# 20_FPGA_Power.net
KiCad netlist of a schematic drawn in Altium Designer
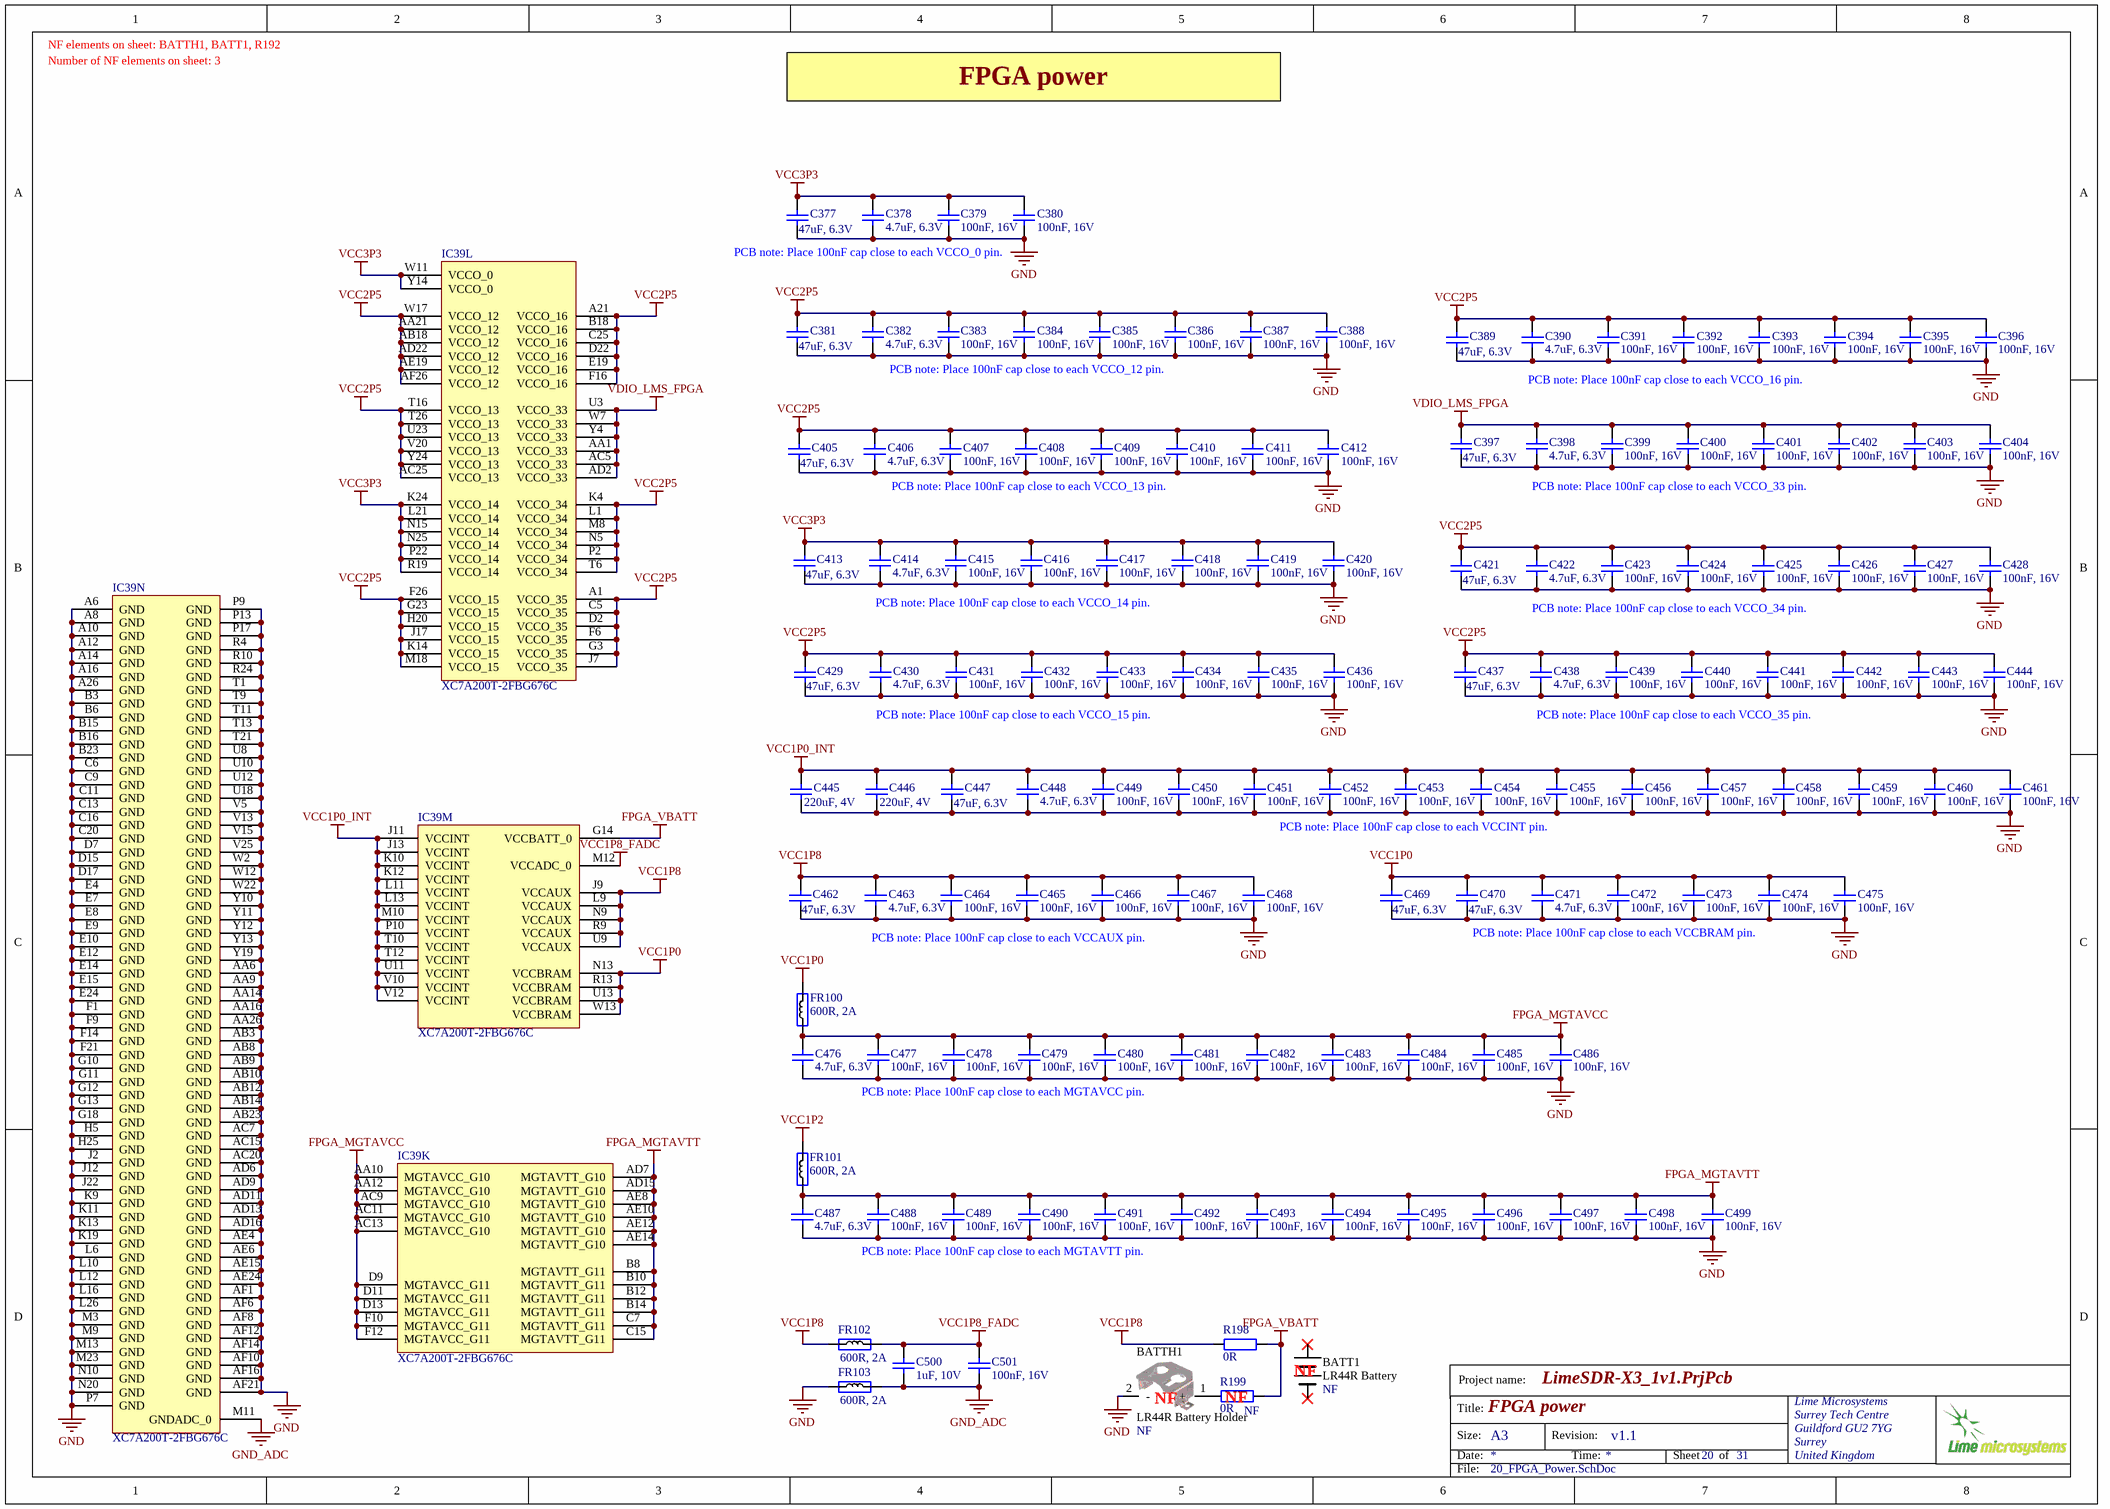
[diagram p0: 20_FPGA_Power.SchDoc]

(export (version "E")
  (design (tool "Eeschema 10.0.6"))
  (components
    (comp (ref "BATT1")
      (value "LR44R Battery")
      (fields (field (name "MANUFACTURER") "Murata") (field (name "ASSEMBLY INFO") "NF"))
      (libsource (lib "LimeMicroAltiumLib_schLib_r03") (part "LR44R_BATTERY"))
    )
    (comp (ref "BATTH1")
      (value "LR44R Battery Holder")
      (footprint "LR44R_BATTERY_HOLDER")
      (fields (field (name "MANUFACTURER") "Keystone Electronics") (field (name "ASSEMBLY INFO") "NF"))
      (libsource (lib "LimeMicroAltiumLib_schLib_r04") (part "LR44R_BATTERY_HOLDER"))
    )
    (comp (ref "C377")
      (value "47uF, 6.3V")
      (footprint "CAP1206")
      (fields
        (field (name "TOLERANCE") "±20%")
        (field (name "MANUFACTURER") "Samsung Electro-Mechanics")
        (field (name "MANUFACTURER PART NUMBER") "CL31A476MQHNNNE")
      )
      (libsource (lib "") (part "Cap_1206_1"))
    )
    (comp (ref "C378")
      (value "4.7uF, 6.3V")
      (footprint "CAP0402")
      (fields
        (field (name "MANUFACTURER") "Murata Electronics North America")
        (field (name "TOLERANCE") "±20%")
      )
      (libsource (lib "LimeMicroAltiumLib_schLib") (part "Cap_0402"))
    )
    (comp (ref "C379")
      (value "100nF, 16V")
      (footprint "CAP0402")
      (fields (field (name "MANUFACTURER") "Murata Electronics") (field (name "TOLERANCE") "10 %"))
      (libsource (lib "LimeMicroAltiumLib_schLib") (part "Cap_0402"))
    )
    (comp (ref "C380")
      (value "100nF, 16V")
      (footprint "CAP0402")
      (fields (field (name "MANUFACTURER") "Murata Electronics") (field (name "TOLERANCE") "10 %"))
      (libsource (lib "LimeMicroAltiumLib_schLib") (part "Cap_0402"))
    )
    (comp (ref "C381")
      (value "47uF, 6.3V")
      (footprint "CAP1206")
      (fields
        (field (name "TOLERANCE") "±20%")
        (field (name "MANUFACTURER") "Samsung Electro-Mechanics")
        (field (name "MANUFACTURER PART NUMBER") "CL31A476MQHNNNE")
      )
      (libsource (lib "") (part "Cap_1206_1"))
    )
    (comp (ref "C382")
      (value "4.7uF, 6.3V")
      (footprint "CAP0402")
      (fields
        (field (name "MANUFACTURER") "Murata Electronics North America")
        (field (name "TOLERANCE") "±20%")
      )
      (libsource (lib "LimeMicroAltiumLib_schLib") (part "Cap_0402"))
    )
    (comp (ref "C383")
      (value "100nF, 16V")
      (footprint "CAP0402")
      (fields (field (name "MANUFACTURER") "Murata Electronics") (field (name "TOLERANCE") "10 %"))
      (libsource (lib "LimeMicroAltiumLib_schLib") (part "Cap_0402"))
    )
    (comp (ref "C384")
      (value "100nF, 16V")
      (footprint "CAP0402")
      (fields (field (name "MANUFACTURER") "Murata Electronics") (field (name "TOLERANCE") "10 %"))
      (libsource (lib "LimeMicroAltiumLib_schLib") (part "Cap_0402"))
    )
    (comp (ref "C385")
      (value "100nF, 16V")
      (footprint "CAP0402")
      (fields (field (name "MANUFACTURER") "Murata Electronics") (field (name "TOLERANCE") "10 %"))
      (libsource (lib "") (part "Cap_0402_2"))
    )
    (comp (ref "C386")
      (value "100nF, 16V")
      (footprint "CAP0402")
      (fields (field (name "MANUFACTURER") "Murata Electronics") (field (name "TOLERANCE") "10 %"))
      (libsource (lib "") (part "Cap_0402_1"))
    )
    (comp (ref "C387")
      (value "100nF, 16V")
      (footprint "CAP0402")
      (fields (field (name "MANUFACTURER") "Murata Electronics") (field (name "TOLERANCE") "10 %"))
      (libsource (lib "") (part "Cap_0402_1"))
    )
    (comp (ref "C388")
      (value "100nF, 16V")
      (footprint "CAP0402")
      (fields (field (name "MANUFACTURER") "Murata Electronics") (field (name "TOLERANCE") "10 %"))
      (libsource (lib "LimeMicroAltiumLib_schLib") (part "Cap_0402"))
    )
    (comp (ref "C389")
      (value "47uF, 6.3V")
      (footprint "CAP1206")
      (fields
        (field (name "TOLERANCE") "±20%")
        (field (name "MANUFACTURER") "Samsung Electro-Mechanics")
        (field (name "MANUFACTURER PART NUMBER") "CL31A476MQHNNNE")
      )
      (libsource (lib "") (part "Cap_1206_1"))
    )
    (comp (ref "C390")
      (value "4.7uF, 6.3V")
      (footprint "CAP0402")
      (fields
        (field (name "MANUFACTURER") "Murata Electronics North America")
        (field (name "TOLERANCE") "±20%")
      )
      (libsource (lib "LimeMicroAltiumLib_schLib") (part "Cap_0402"))
    )
    (comp (ref "C391")
      (value "100nF, 16V")
      (footprint "CAP0402")
      (fields (field (name "MANUFACTURER") "Murata Electronics") (field (name "TOLERANCE") "10 %"))
      (libsource (lib "LimeMicroAltiumLib_schLib") (part "Cap_0402"))
    )
    (comp (ref "C392")
      (value "100nF, 16V")
      (footprint "CAP0402")
      (fields (field (name "MANUFACTURER") "Murata Electronics") (field (name "TOLERANCE") "10 %"))
      (libsource (lib "LimeMicroAltiumLib_schLib") (part "Cap_0402"))
    )
    (comp (ref "C393")
      (value "100nF, 16V")
      (footprint "CAP0402")
      (fields (field (name "MANUFACTURER") "Murata Electronics") (field (name "TOLERANCE") "10 %"))
      (libsource (lib "") (part "Cap_0402_2"))
    )
    (comp (ref "C394")
      (value "100nF, 16V")
      (footprint "CAP0402")
      (fields (field (name "MANUFACTURER") "Murata Electronics") (field (name "TOLERANCE") "10 %"))
      (libsource (lib "") (part "Cap_0402_1"))
    )
    (comp (ref "C395")
      (value "100nF, 16V")
      (footprint "CAP0402")
      (fields (field (name "MANUFACTURER") "Murata Electronics") (field (name "TOLERANCE") "10 %"))
      (libsource (lib "") (part "Cap_0402_1"))
    )
    (comp (ref "C396")
      (value "100nF, 16V")
      (footprint "CAP0402")
      (fields (field (name "MANUFACTURER") "Murata Electronics") (field (name "TOLERANCE") "10 %"))
      (libsource (lib "LimeMicroAltiumLib_schLib") (part "Cap_0402"))
    )
    (comp (ref "C397")
      (value "47uF, 6.3V")
      (footprint "CAP1206")
      (fields
        (field (name "TOLERANCE") "±20%")
        (field (name "MANUFACTURER") "Samsung Electro-Mechanics")
        (field (name "MANUFACTURER PART NUMBER") "CL31A476MQHNNNE")
      )
      (libsource (lib "LimeFPGAboard_schLib") (part "Cap_1206"))
    )
    (comp (ref "C398")
      (value "4.7uF, 6.3V")
      (footprint "CAP0402")
      (fields
        (field (name "MANUFACTURER") "Murata Electronics North America")
        (field (name "TOLERANCE") "±20%")
      )
      (libsource (lib "LimeMicroAltiumLib_schLib") (part "Cap_0402"))
    )
    (comp (ref "C399")
      (value "100nF, 16V")
      (footprint "CAP0402")
      (fields (field (name "MANUFACTURER") "Murata Electronics") (field (name "TOLERANCE") "10 %"))
      (libsource (lib "") (part "Cap_0402_1"))
    )
    (comp (ref "C400")
      (value "100nF, 16V")
      (footprint "CAP0402")
      (fields (field (name "MANUFACTURER") "Murata Electronics") (field (name "TOLERANCE") "10 %"))
      (libsource (lib "LimeMicroAltiumLib_schLib") (part "Cap_0402"))
    )
    (comp (ref "C401")
      (value "100nF, 16V")
      (footprint "CAP0402")
      (fields (field (name "MANUFACTURER") "Murata Electronics") (field (name "TOLERANCE") "10 %"))
      (libsource (lib "LimeMicroAltiumLib_schLib") (part "Cap_0402"))
    )
    (comp (ref "C402")
      (value "100nF, 16V")
      (footprint "CAP0402")
      (fields (field (name "MANUFACTURER") "Murata Electronics") (field (name "TOLERANCE") "10 %"))
      (libsource (lib "") (part "Cap_0402_2"))
    )
    (comp (ref "C403")
      (value "100nF, 16V")
      (footprint "CAP0402")
      (fields (field (name "MANUFACTURER") "Murata Electronics") (field (name "TOLERANCE") "10 %"))
      (libsource (lib "") (part "Cap_0402_1"))
    )
    (comp (ref "C404")
      (value "100nF, 16V")
      (footprint "CAP0402")
      (fields (field (name "MANUFACTURER") "Murata Electronics") (field (name "TOLERANCE") "10 %"))
      (libsource (lib "") (part "Cap_0402_1"))
    )
    (comp (ref "C405")
      (value "47uF, 6.3V")
      (footprint "CAP1206")
      (fields
        (field (name "TOLERANCE") "±20%")
        (field (name "MANUFACTURER") "Samsung Electro-Mechanics")
        (field (name "MANUFACTURER PART NUMBER") "CL31A476MQHNNNE")
      )
      (libsource (lib "") (part "Cap_1206_2"))
    )
    (comp (ref "C406")
      (value "4.7uF, 6.3V")
      (footprint "CAP0402")
      (fields
        (field (name "MANUFACTURER") "Murata Electronics North America")
        (field (name "TOLERANCE") "±20%")
      )
      (libsource (lib "") (part "Cap_0402_1"))
    )
    (comp (ref "C407")
      (value "100nF, 16V")
      (footprint "CAP0402")
      (fields (field (name "MANUFACTURER") "Murata Electronics") (field (name "TOLERANCE") "10 %"))
      (libsource (lib "") (part "Cap_0402_2"))
    )
    (comp (ref "C408")
      (value "100nF, 16V")
      (footprint "CAP0402")
      (fields (field (name "MANUFACTURER") "Murata Electronics") (field (name "TOLERANCE") "10 %"))
      (libsource (lib "") (part "Cap_0402_1"))
    )
    (comp (ref "C409")
      (value "100nF, 16V")
      (footprint "CAP0402")
      (fields (field (name "MANUFACTURER") "Murata Electronics") (field (name "TOLERANCE") "10 %"))
      (libsource (lib "") (part "Cap_0402_1"))
    )
    (comp (ref "C410")
      (value "100nF, 16V")
      (footprint "CAP0402")
      (fields (field (name "MANUFACTURER") "Murata Electronics") (field (name "TOLERANCE") "10 %"))
      (libsource (lib "LimeMicroAltiumLib_schLib") (part "Cap_0402"))
    )
    (comp (ref "C411")
      (value "100nF, 16V")
      (footprint "CAP0402")
      (fields (field (name "MANUFACTURER") "Murata Electronics") (field (name "TOLERANCE") "10 %"))
      (libsource (lib "LimeMicroAltiumLib_schLib") (part "Cap_0402"))
    )
    (comp (ref "C412")
      (value "100nF, 16V")
      (footprint "CAP0402")
      (fields (field (name "MANUFACTURER") "Murata Electronics") (field (name "TOLERANCE") "10 %"))
      (libsource (lib "") (part "Cap_0402_2"))
    )
    (comp (ref "C413")
      (value "47uF, 6.3V")
      (footprint "CAP1206")
      (fields
        (field (name "TOLERANCE") "±20%")
        (field (name "MANUFACTURER") "Samsung Electro-Mechanics")
        (field (name "MANUFACTURER PART NUMBER") "CL31A476MQHNNNE")
      )
      (libsource (lib "") (part "Cap_1206_2"))
    )
    (comp (ref "C414")
      (value "4.7uF, 6.3V")
      (footprint "CAP0402")
      (fields
        (field (name "MANUFACTURER") "Murata Electronics North America")
        (field (name "TOLERANCE") "±20%")
      )
      (libsource (lib "") (part "Cap_0402_1"))
    )
    (comp (ref "C415")
      (value "100nF, 16V")
      (footprint "CAP0402")
      (fields (field (name "MANUFACTURER") "Murata Electronics") (field (name "TOLERANCE") "10 %"))
      (libsource (lib "") (part "Cap_0402_2"))
    )
    (comp (ref "C416")
      (value "100nF, 16V")
      (footprint "CAP0402")
      (fields (field (name "MANUFACTURER") "Murata Electronics") (field (name "TOLERANCE") "10 %"))
      (libsource (lib "") (part "Cap_0402_1"))
    )
    (comp (ref "C417")
      (value "100nF, 16V")
      (footprint "CAP0402")
      (fields (field (name "MANUFACTURER") "Murata Electronics") (field (name "TOLERANCE") "10 %"))
      (libsource (lib "") (part "Cap_0402_1"))
    )
    (comp (ref "C418")
      (value "100nF, 16V")
      (footprint "CAP0402")
      (fields (field (name "MANUFACTURER") "Murata Electronics") (field (name "TOLERANCE") "10 %"))
      (libsource (lib "LimeMicroAltiumLib_schLib") (part "Cap_0402"))
    )
    (comp (ref "C419")
      (value "100nF, 16V")
      (footprint "CAP0402")
      (fields (field (name "MANUFACTURER") "Murata Electronics") (field (name "TOLERANCE") "10 %"))
      (libsource (lib "LimeMicroAltiumLib_schLib") (part "Cap_0402"))
    )
    (comp (ref "C420")
      (value "100nF, 16V")
      (footprint "CAP0402")
      (fields (field (name "MANUFACTURER") "Murata Electronics") (field (name "TOLERANCE") "10 %"))
      (libsource (lib "") (part "Cap_0402_2"))
    )
    (comp (ref "C421")
      (value "47uF, 6.3V")
      (footprint "CAP1206")
      (fields
        (field (name "TOLERANCE") "±20%")
        (field (name "MANUFACTURER") "Samsung Electro-Mechanics")
        (field (name "MANUFACTURER PART NUMBER") "CL31A476MQHNNNE")
      )
      (libsource (lib "LimeFPGAboard_schLib") (part "Cap_1206"))
    )
    (comp (ref "C422")
      (value "4.7uF, 6.3V")
      (footprint "CAP0402")
      (fields
        (field (name "MANUFACTURER") "Murata Electronics North America")
        (field (name "TOLERANCE") "±20%")
      )
      (libsource (lib "LimeMicroAltiumLib_schLib") (part "Cap_0402"))
    )
    (comp (ref "C423")
      (value "100nF, 16V")
      (footprint "CAP0402")
      (fields (field (name "MANUFACTURER") "Murata Electronics") (field (name "TOLERANCE") "10 %"))
      (libsource (lib "") (part "Cap_0402_1"))
    )
    (comp (ref "C424")
      (value "100nF, 16V")
      (footprint "CAP0402")
      (fields (field (name "MANUFACTURER") "Murata Electronics") (field (name "TOLERANCE") "10 %"))
      (libsource (lib "LimeMicroAltiumLib_schLib") (part "Cap_0402"))
    )
    (comp (ref "C425")
      (value "100nF, 16V")
      (footprint "CAP0402")
      (fields (field (name "MANUFACTURER") "Murata Electronics") (field (name "TOLERANCE") "10 %"))
      (libsource (lib "LimeMicroAltiumLib_schLib") (part "Cap_0402"))
    )
    (comp (ref "C426")
      (value "100nF, 16V")
      (footprint "CAP0402")
      (fields (field (name "MANUFACTURER") "Murata Electronics") (field (name "TOLERANCE") "10 %"))
      (libsource (lib "") (part "Cap_0402_2"))
    )
    (comp (ref "C427")
      (value "100nF, 16V")
      (footprint "CAP0402")
      (fields (field (name "MANUFACTURER") "Murata Electronics") (field (name "TOLERANCE") "10 %"))
      (libsource (lib "") (part "Cap_0402_1"))
    )
    (comp (ref "C428")
      (value "100nF, 16V")
      (footprint "CAP0402")
      (fields (field (name "MANUFACTURER") "Murata Electronics") (field (name "TOLERANCE") "10 %"))
      (libsource (lib "") (part "Cap_0402_1"))
    )
    (comp (ref "C429")
      (value "47uF, 6.3V")
      (footprint "CAP1206")
      (fields
        (field (name "TOLERANCE") "±20%")
        (field (name "MANUFACTURER") "Samsung Electro-Mechanics")
        (field (name "MANUFACTURER PART NUMBER") "CL31A476MQHNNNE")
      )
      (libsource (lib "") (part "Cap_1206_2"))
    )
    (comp (ref "C430")
      (value "4.7uF, 6.3V")
      (footprint "CAP0402")
      (fields
        (field (name "MANUFACTURER") "Murata Electronics North America")
        (field (name "TOLERANCE") "±20%")
      )
      (libsource (lib "") (part "Cap_0402_1"))
    )
    (comp (ref "C431")
      (value "100nF, 16V")
      (footprint "CAP0402")
      (fields (field (name "MANUFACTURER") "Murata Electronics") (field (name "TOLERANCE") "10 %"))
      (libsource (lib "") (part "Cap_0402_2"))
    )
    (comp (ref "C432")
      (value "100nF, 16V")
      (footprint "CAP0402")
      (fields (field (name "MANUFACTURER") "Murata Electronics") (field (name "TOLERANCE") "10 %"))
      (libsource (lib "") (part "Cap_0402_1"))
    )
    (comp (ref "C433")
      (value "100nF, 16V")
      (footprint "CAP0402")
      (fields (field (name "MANUFACTURER") "Murata Electronics") (field (name "TOLERANCE") "10 %"))
      (libsource (lib "") (part "Cap_0402_1"))
    )
    (comp (ref "C434")
      (value "100nF, 16V")
      (footprint "CAP0402")
      (fields (field (name "MANUFACTURER") "Murata Electronics") (field (name "TOLERANCE") "10 %"))
      (libsource (lib "LimeMicroAltiumLib_schLib") (part "Cap_0402"))
    )
    (comp (ref "C435")
      (value "100nF, 16V")
      (footprint "CAP0402")
      (fields (field (name "MANUFACTURER") "Murata Electronics") (field (name "TOLERANCE") "10 %"))
      (libsource (lib "LimeMicroAltiumLib_schLib") (part "Cap_0402"))
    )
    (comp (ref "C436")
      (value "100nF, 16V")
      (footprint "CAP0402")
      (fields (field (name "MANUFACTURER") "Murata Electronics") (field (name "TOLERANCE") "10 %"))
      (libsource (lib "") (part "Cap_0402_2"))
    )
    (comp (ref "C437")
      (value "47uF, 6.3V")
      (footprint "CAP1206")
      (fields
        (field (name "TOLERANCE") "±20%")
        (field (name "MANUFACTURER") "Samsung Electro-Mechanics")
        (field (name "MANUFACTURER PART NUMBER") "CL31A476MQHNNNE")
      )
      (libsource (lib "") (part "Cap_1206_2"))
    )
    (comp (ref "C438")
      (value "4.7uF, 6.3V")
      (footprint "CAP0402")
      (fields
        (field (name "MANUFACTURER") "Murata Electronics North America")
        (field (name "TOLERANCE") "±20%")
      )
      (libsource (lib "") (part "Cap_0402_2"))
    )
    (comp (ref "C439")
      (value "100nF, 16V")
      (footprint "CAP0402")
      (fields (field (name "MANUFACTURER") "Murata Electronics") (field (name "TOLERANCE") "10 %"))
      (libsource (lib "") (part "Cap_0402_1"))
    )
    (comp (ref "C440")
      (value "100nF, 16V")
      (footprint "CAP0402")
      (fields (field (name "MANUFACTURER") "Murata Electronics") (field (name "TOLERANCE") "10 %"))
      (libsource (lib "") (part "Cap_0402_1"))
    )
    (comp (ref "C441")
      (value "100nF, 16V")
      (footprint "CAP0402")
      (fields (field (name "MANUFACTURER") "Murata Electronics") (field (name "TOLERANCE") "10 %"))
      (libsource (lib "LimeMicroAltiumLib_schLib") (part "Cap_0402"))
    )
    (comp (ref "C442")
      (value "100nF, 16V")
      (footprint "CAP0402")
      (fields (field (name "MANUFACTURER") "Murata Electronics") (field (name "TOLERANCE") "10 %"))
      (libsource (lib "LimeMicroAltiumLib_schLib") (part "Cap_0402"))
    )
    (comp (ref "C443")
      (value "100nF, 16V")
      (footprint "CAP0402")
      (fields (field (name "MANUFACTURER") "Murata Electronics") (field (name "TOLERANCE") "10 %"))
      (libsource (lib "") (part "Cap_0402_2"))
    )
    (comp (ref "C444")
      (value "100nF, 16V")
      (footprint "CAP0402")
      (fields (field (name "MANUFACTURER") "Murata Electronics") (field (name "TOLERANCE") "10 %"))
      (libsource (lib "") (part "Cap_0402_1"))
    )
    (comp (ref "C445")
      (value "220uF, 4V")
      (footprint "CAP1206")
      (fields
        (field (name "MANUFACTURER") "Murata Electronics North America")
        (field (name "TOLERANCE") "±20%")
      )
      (libsource (lib "LimeFPGAboard_schLib") (part "Cap_1206"))
    )
    (comp (ref "C446")
      (value "220uF, 4V")
      (footprint "CAP1206")
      (fields
        (field (name "MANUFACTURER") "Murata Electronics North America")
        (field (name "TOLERANCE") "±20%")
      )
      (libsource (lib "") (part "Cap_1206_1"))
    )
    (comp (ref "C447")
      (value "47uF, 6.3V")
      (footprint "CAP1206")
      (fields
        (field (name "TOLERANCE") "±20%")
        (field (name "MANUFACTURER") "Samsung Electro-Mechanics")
        (field (name "MANUFACTURER PART NUMBER") "CL31A476MQHNNNE")
      )
      (libsource (lib "") (part "Cap_1206_1"))
    )
    (comp (ref "C448")
      (value "4.7uF, 6.3V")
      (footprint "CAP0402")
      (fields
        (field (name "MANUFACTURER") "Murata Electronics North America")
        (field (name "TOLERANCE") "±20%")
      )
      (libsource (lib "") (part "Cap_0402_1"))
    )
    (comp (ref "C449")
      (value "100nF, 16V")
      (footprint "CAP0402")
      (fields (field (name "MANUFACTURER") "Murata Electronics") (field (name "TOLERANCE") "10 %"))
      (libsource (lib "LimeMicroAltiumLib_schLib") (part "Cap_0402"))
    )
    (comp (ref "C450")
      (value "100nF, 16V")
      (footprint "CAP0402")
      (fields (field (name "MANUFACTURER") "Murata Electronics") (field (name "TOLERANCE") "10 %"))
      (libsource (lib "") (part "Cap_0402_2"))
    )
    (comp (ref "C451")
      (value "100nF, 16V")
      (footprint "CAP0402")
      (fields (field (name "MANUFACTURER") "Murata Electronics") (field (name "TOLERANCE") "10 %"))
      (libsource (lib "") (part "Cap_0402_1"))
    )
    (comp (ref "C452")
      (value "100nF, 16V")
      (footprint "CAP0402")
      (fields (field (name "MANUFACTURER") "Murata Electronics") (field (name "TOLERANCE") "10 %"))
      (libsource (lib "") (part "Cap_0402_1"))
    )
    (comp (ref "C453")
      (value "100nF, 16V")
      (footprint "CAP0402")
      (fields (field (name "MANUFACTURER") "Murata Electronics") (field (name "TOLERANCE") "10 %"))
      (libsource (lib "LimeMicroAltiumLib_schLib") (part "Cap_0402"))
    )
    (comp (ref "C454")
      (value "100nF, 16V")
      (footprint "CAP0402")
      (fields (field (name "MANUFACTURER") "Murata Electronics") (field (name "TOLERANCE") "10 %"))
      (libsource (lib "LimeMicroAltiumLib_schLib") (part "Cap_0402"))
    )
    (comp (ref "C455")
      (value "100nF, 16V")
      (footprint "CAP0402")
      (fields (field (name "MANUFACTURER") "Murata Electronics") (field (name "TOLERANCE") "10 %"))
      (libsource (lib "") (part "Cap_0402_2"))
    )
    (comp (ref "C456")
      (value "100nF, 16V")
      (footprint "CAP0402")
      (fields (field (name "MANUFACTURER") "Murata Electronics") (field (name "TOLERANCE") "10 %"))
      (libsource (lib "") (part "Cap_0402_1"))
    )
    (comp (ref "C457")
      (value "100nF, 16V")
      (footprint "CAP0402")
      (fields (field (name "MANUFACTURER") "Murata Electronics") (field (name "TOLERANCE") "10 %"))
      (libsource (lib "") (part "Cap_0402_1"))
    )
    (comp (ref "C458")
      (value "100nF, 16V")
      (footprint "CAP0402")
      (fields (field (name "MANUFACTURER") "Murata Electronics") (field (name "TOLERANCE") "10 %"))
      (libsource (lib "LimeMicroAltiumLib_schLib") (part "Cap_0402"))
    )
    (comp (ref "C459")
      (value "100nF, 16V")
      (footprint "CAP0402")
      (fields (field (name "MANUFACTURER") "Murata Electronics") (field (name "TOLERANCE") "10 %"))
      (libsource (lib "LimeMicroAltiumLib_schLib") (part "Cap_0402"))
    )
    (comp (ref "C460")
      (value "100nF, 16V")
      (footprint "CAP0402")
      (fields (field (name "MANUFACTURER") "Murata Electronics") (field (name "TOLERANCE") "10 %"))
      (libsource (lib "") (part "Cap_0402_2"))
    )
    (comp (ref "C461")
      (value "100nF, 16V")
      (footprint "CAP0402")
      (fields (field (name "MANUFACTURER") "Murata Electronics") (field (name "TOLERANCE") "10 %"))
      (libsource (lib "") (part "Cap_0402_1"))
    )
    (comp (ref "C462")
      (value "47uF, 6.3V")
      (footprint "CAP1206")
      (fields
        (field (name "TOLERANCE") "±20%")
        (field (name "MANUFACTURER") "Samsung Electro-Mechanics")
        (field (name "MANUFACTURER PART NUMBER") "CL31A476MQHNNNE")
      )
      (libsource (lib "") (part "Cap_1206_2"))
    )
    (comp (ref "C463")
      (value "4.7uF, 6.3V")
      (footprint "CAP0402")
      (fields
        (field (name "MANUFACTURER") "Murata Electronics North America")
        (field (name "TOLERANCE") "±20%")
      )
      (libsource (lib "") (part "Cap_0402_1"))
    )
    (comp (ref "C464")
      (value "100nF, 16V")
      (footprint "CAP0402")
      (fields (field (name "MANUFACTURER") "Murata Electronics") (field (name "TOLERANCE") "10 %"))
      (libsource (lib "") (part "Cap_0402_2"))
    )
    (comp (ref "C465")
      (value "100nF, 16V")
      (footprint "CAP0402")
      (fields (field (name "MANUFACTURER") "Murata Electronics") (field (name "TOLERANCE") "10 %"))
      (libsource (lib "") (part "Cap_0402_1"))
    )
    (comp (ref "C466")
      (value "100nF, 16V")
      (footprint "CAP0402")
      (fields (field (name "MANUFACTURER") "Murata Electronics") (field (name "TOLERANCE") "10 %"))
      (libsource (lib "") (part "Cap_0402_1"))
    )
    (comp (ref "C467")
      (value "100nF, 16V")
      (footprint "CAP0402")
      (fields (field (name "MANUFACTURER") "Murata Electronics") (field (name "TOLERANCE") "10 %"))
      (libsource (lib "LimeMicroAltiumLib_schLib") (part "Cap_0402"))
    )
    (comp (ref "C468")
      (value "100nF, 16V")
      (footprint "CAP0402")
      (fields (field (name "MANUFACTURER") "Murata Electronics") (field (name "TOLERANCE") "10 %"))
      (libsource (lib "LimeMicroAltiumLib_schLib") (part "Cap_0402"))
    )
    (comp (ref "C469")
      (value "47uF, 6.3V")
      (footprint "CAP1206")
      (fields
        (field (name "TOLERANCE") "±20%")
        (field (name "MANUFACTURER") "Samsung Electro-Mechanics")
        (field (name "MANUFACTURER PART NUMBER") "CL31A476MQHNNNE")
      )
      (libsource (lib "") (part "Cap_1206_2"))
    )
    (comp (ref "C470")
      (value "47uF, 6.3V")
      (footprint "CAP1206")
      (fields
        (field (name "TOLERANCE") "±20%")
        (field (name "MANUFACTURER") "Samsung Electro-Mechanics")
        (field (name "MANUFACTURER PART NUMBER") "CL31A476MQHNNNE")
      )
      (libsource (lib "LimeFPGAboard_schLib") (part "Cap_1206"))
    )
    (comp (ref "C471")
      (value "4.7uF, 6.3V")
      (footprint "CAP0402")
      (fields
        (field (name "MANUFACTURER") "Murata Electronics North America")
        (field (name "TOLERANCE") "±20%")
      )
      (libsource (lib "LimeMicroAltiumLib_schLib") (part "Cap_0402"))
    )
    (comp (ref "C472")
      (value "100nF, 16V")
      (footprint "CAP0402")
      (fields (field (name "MANUFACTURER") "Murata Electronics") (field (name "TOLERANCE") "10 %"))
      (libsource (lib "") (part "Cap_0402_1"))
    )
    (comp (ref "C473")
      (value "100nF, 16V")
      (footprint "CAP0402")
      (fields (field (name "MANUFACTURER") "Murata Electronics") (field (name "TOLERANCE") "10 %"))
      (libsource (lib "LimeMicroAltiumLib_schLib") (part "Cap_0402"))
    )
    (comp (ref "C474")
      (value "100nF, 16V")
      (footprint "CAP0402")
      (fields (field (name "MANUFACTURER") "Murata Electronics") (field (name "TOLERANCE") "10 %"))
      (libsource (lib "LimeMicroAltiumLib_schLib") (part "Cap_0402"))
    )
    (comp (ref "C475")
      (value "100nF, 16V")
      (footprint "CAP0402")
      (fields (field (name "MANUFACTURER") "Murata Electronics") (field (name "TOLERANCE") "10 %"))
      (libsource (lib "LimeMicroAltiumLib_schLib") (part "Cap_0402"))
    )
    (comp (ref "C476")
      (value "4.7uF, 6.3V")
      (footprint "CAP0402")
      (fields
        (field (name "MANUFACTURER") "Murata Electronics North America")
        (field (name "TOLERANCE") "±20%")
      )
      (libsource (lib "") (part "Cap_0402_2"))
    )
    (comp (ref "C477")
      (value "100nF, 16V")
      (footprint "CAP0402")
      (fields (field (name "MANUFACTURER") "Murata Electronics") (field (name "TOLERANCE") "10 %"))
      (libsource (lib "") (part "Cap_0402_1"))
    )
    (comp (ref "C478")
      (value "100nF, 16V")
      (footprint "CAP0402")
      (fields (field (name "MANUFACTURER") "Murata Electronics") (field (name "TOLERANCE") "10 %"))
      (libsource (lib "") (part "Cap_0402_1"))
    )
    (comp (ref "C479")
      (value "100nF, 16V")
      (footprint "CAP0402")
      (fields (field (name "MANUFACTURER") "Murata Electronics") (field (name "TOLERANCE") "10 %"))
      (libsource (lib "LimeMicroAltiumLib_schLib") (part "Cap_0402"))
    )
    (comp (ref "C480")
      (value "100nF, 16V")
      (footprint "CAP0402")
      (fields (field (name "MANUFACTURER") "Murata Electronics") (field (name "TOLERANCE") "10 %"))
      (libsource (lib "LimeMicroAltiumLib_schLib") (part "Cap_0402"))
    )
    (comp (ref "C481")
      (value "100nF, 16V")
      (footprint "CAP0402")
      (fields (field (name "MANUFACTURER") "Murata Electronics") (field (name "TOLERANCE") "10 %"))
      (libsource (lib "") (part "Cap_0402_3"))
    )
    (comp (ref "C482")
      (value "100nF, 16V")
      (footprint "CAP0402")
      (fields (field (name "MANUFACTURER") "Murata Electronics") (field (name "TOLERANCE") "10 %"))
      (libsource (lib "") (part "Cap_0402_1"))
    )
    (comp (ref "C483")
      (value "100nF, 16V")
      (footprint "CAP0402")
      (fields (field (name "MANUFACTURER") "Murata Electronics") (field (name "TOLERANCE") "10 %"))
      (libsource (lib "") (part "Cap_0402_1"))
    )
    (comp (ref "C484")
      (value "100nF, 16V")
      (footprint "CAP0402")
      (fields (field (name "MANUFACTURER") "Murata Electronics") (field (name "TOLERANCE") "10 %"))
      (libsource (lib "LimeMicroAltiumLib_schLib") (part "Cap_0402"))
    )
    (comp (ref "C485")
      (value "100nF, 16V")
      (footprint "CAP0402")
      (fields (field (name "MANUFACTURER") "Murata Electronics") (field (name "TOLERANCE") "10 %"))
      (libsource (lib "LimeMicroAltiumLib_schLib") (part "Cap_0402"))
    )
    (comp (ref "C486")
      (value "100nF, 16V")
      (footprint "CAP0402")
      (fields (field (name "MANUFACTURER") "Murata Electronics") (field (name "TOLERANCE") "10 %"))
      (libsource (lib "") (part "Cap_0402_3"))
    )
    (comp (ref "C487")
      (value "4.7uF, 6.3V")
      (footprint "CAP0402")
      (fields
        (field (name "MANUFACTURER") "Murata Electronics North America")
        (field (name "TOLERANCE") "±20%")
      )
      (libsource (lib "") (part "Cap_0402_1"))
    )
    (comp (ref "C488")
      (value "100nF, 16V")
      (footprint "CAP0402")
      (fields (field (name "MANUFACTURER") "Murata Electronics") (field (name "TOLERANCE") "10 %"))
      (libsource (lib "") (part "Cap_0402_1"))
    )
    (comp (ref "C489")
      (value "100nF, 16V")
      (footprint "CAP0402")
      (fields (field (name "MANUFACTURER") "Murata Electronics") (field (name "TOLERANCE") "10 %"))
      (libsource (lib "LimeMicroAltiumLib_schLib") (part "Cap_0402"))
    )
    (comp (ref "C490")
      (value "100nF, 16V")
      (footprint "CAP0402")
      (fields (field (name "MANUFACTURER") "Murata Electronics") (field (name "TOLERANCE") "10 %"))
      (libsource (lib "LimeMicroAltiumLib_schLib") (part "Cap_0402"))
    )
    (comp (ref "C491")
      (value "100nF, 16V")
      (footprint "CAP0402")
      (fields (field (name "MANUFACTURER") "Murata Electronics") (field (name "TOLERANCE") "10 %"))
      (libsource (lib "") (part "Cap_0402_2"))
    )
    (comp (ref "C492")
      (value "100nF, 16V")
      (footprint "CAP0402")
      (fields (field (name "MANUFACTURER") "Murata Electronics") (field (name "TOLERANCE") "10 %"))
      (libsource (lib "") (part "Cap_0402_1"))
    )
    (comp (ref "C493")
      (value "100nF, 16V")
      (footprint "CAP0402")
      (fields (field (name "MANUFACTURER") "Murata Electronics") (field (name "TOLERANCE") "10 %"))
      (libsource (lib "") (part "Cap_0402_1"))
    )
    (comp (ref "C494")
      (value "100nF, 16V")
      (footprint "CAP0402")
      (fields (field (name "MANUFACTURER") "Murata Electronics") (field (name "TOLERANCE") "10 %"))
      (libsource (lib "") (part "Cap_0402_1"))
    )
    (comp (ref "C495")
      (value "100nF, 16V")
      (footprint "CAP0402")
      (fields (field (name "MANUFACTURER") "Murata Electronics") (field (name "TOLERANCE") "10 %"))
      (libsource (lib "LimeMicroAltiumLib_schLib") (part "Cap_0402"))
    )
    (comp (ref "C496")
      (value "100nF, 16V")
      (footprint "CAP0402")
      (fields (field (name "MANUFACTURER") "Murata Electronics") (field (name "TOLERANCE") "10 %"))
      (libsource (lib "LimeMicroAltiumLib_schLib") (part "Cap_0402"))
    )
    (comp (ref "C497")
      (value "100nF, 16V")
      (footprint "CAP0402")
      (fields (field (name "MANUFACTURER") "Murata Electronics") (field (name "TOLERANCE") "10 %"))
      (libsource (lib "") (part "Cap_0402_3"))
    )
    (comp (ref "C498")
      (value "100nF, 16V")
      (footprint "CAP0402")
      (fields (field (name "MANUFACTURER") "Murata Electronics") (field (name "TOLERANCE") "10 %"))
      (libsource (lib "LimeMicroAltiumLib_schLib") (part "Cap_0402"))
    )
    (comp (ref "C499")
      (value "100nF, 16V")
      (footprint "CAP0402")
      (fields (field (name "MANUFACTURER") "Murata Electronics") (field (name "TOLERANCE") "10 %"))
      (libsource (lib "") (part "Cap_0402_3"))
    )
    (comp (ref "C500")
      (value "1uF, 10V")
      (footprint "CAP0402")
      (fields (field (name "MANUFACTURER") "TDK"))
      (libsource (lib "") (part "Cap_0402_2"))
    )
    (comp (ref "C501")
      (value "100nF, 16V")
      (footprint "CAP0402")
      (fields (field (name "MANUFACTURER") "Murata Electronics") (field (name "TOLERANCE") "10 %"))
      (libsource (lib "") (part "Cap_0402_1"))
    )
    (comp (ref "FR100")
      (value "600R, 2A")
      (footprint "RES0805")
      (fields (field (name "MANUFACTURER") "TDK Corporation"))
      (libsource (lib "LimeMicroAltiumLib_schLib") (part "Ferrite"))
    )
    (comp (ref "FR101")
      (value "600R, 2A")
      (footprint "RES0805")
      (fields (field (name "MANUFACTURER") "TDK Corporation"))
      (libsource (lib "LimeMicroAltiumLib_schLib") (part "Ferrite"))
    )
    (comp (ref "FR102")
      (value "600R, 2A")
      (footprint "RES0805")
      (fields (field (name "MANUFACTURER") "TDK Corporation"))
      (libsource (lib "LimeMicroAltiumLib_schLib") (part "Ferrite"))
    )
    (comp (ref "FR103")
      (value "600R, 2A")
      (footprint "RES0805")
      (fields (field (name "MANUFACTURER") "TDK Corporation"))
      (libsource (lib "LimeMicroAltiumLib_schLib") (part "Ferrite"))
    )
    (comp (ref "IC39")
      (value "XC7A200T-2FBG676C")
      (footprint "XC7A200T-2FBG676C_FBG676")
      (description "Artix-7 FPGA, 400 User I/Os, 8 GTP, 676-Ball BGA, Speed Grade 2, Commercial Grade, Pb-Free")
      (fields (field (name "MANUFACTURER") "Xilinx"))
      (libsource (lib "LimeMicroAltiumLib_schLib_r02") (part "XC7A200T-2FBG676C"))
    )
    (comp (ref "R198")
      (value "0R")
      (footprint "RES0402")
      (fields (field (name "MANUFACTURER") "Yageo") (field (name "TOLERANCE") "Jumper"))
      (libsource (lib "LimeMicroAltiumLib_schLib") (part "Res_0402"))
    )
    (comp (ref "R199")
      (value "0R")
      (footprint "RES0402")
      (fields
        (field (name "ASSEMBLY INFO") "NF")
        (field (name "MANUFACTURER") "Yageo")
        (field (name "TOLERANCE") "Jumper")
      )
      (libsource (lib "LimeMicroAltiumLib_schLib") (part "Res_0402"))
    )
  )
  (nets
    (net (code "1") (name "FPGA_MGTAVCC") (class "Default")
      (node (ref "C476") (pin "2") (pinfunction "2_2") (pintype "passive"))
      (node (ref "C477") (pin "1") (pinfunction "1_1") (pintype "passive"))
      (node (ref "C478") (pin "1") (pinfunction "1_1") (pintype "passive"))
      (node (ref "C479") (pin "1") (pinfunction "1_1") (pintype "passive"))
      (node (ref "C480") (pin "1") (pinfunction "1_1") (pintype "passive"))
      (node (ref "C481") (pin "1") (pinfunction "1_1") (pintype "passive"))
      (node (ref "C482") (pin "1") (pinfunction "1_1") (pintype "passive"))
      (node (ref "C483") (pin "1") (pinfunction "1_1") (pintype "passive"))
      (node (ref "C484") (pin "1") (pinfunction "1_1") (pintype "passive"))
      (node (ref "C485") (pin "1") (pinfunction "1_1") (pintype "passive"))
      (node (ref "C486") (pin "1") (pinfunction "1_1") (pintype "passive"))
      (node (ref "FR100") (pin "1") (pinfunction "1_1") (pintype "passive"))
      (node (ref "IC39") (pin "AA10") (pinfunction "MGTAVCC_G10_AA10") (pintype "power_in"))
      (node (ref "IC39") (pin "AA12") (pinfunction "MGTAVCC_G10_AA12") (pintype "power_in"))
      (node (ref "IC39") (pin "AC11") (pinfunction "MGTAVCC_G10_AC11") (pintype "power_in"))
      (node (ref "IC39") (pin "AC13") (pinfunction "MGTAVCC_G10_AC13") (pintype "power_in"))
      (node (ref "IC39") (pin "AC9") (pinfunction "MGTAVCC_G10_AC9") (pintype "power_in"))
      (node (ref "IC39") (pin "D11") (pinfunction "MGTAVCC_G11_D11") (pintype "power_in"))
      (node (ref "IC39") (pin "D13") (pinfunction "MGTAVCC_G11_D13") (pintype "power_in"))
      (node (ref "IC39") (pin "D9") (pinfunction "MGTAVCC_G11_D9") (pintype "power_in"))
      (node (ref "IC39") (pin "F10") (pinfunction "MGTAVCC_G11_F10") (pintype "power_in"))
      (node (ref "IC39") (pin "F12") (pinfunction "MGTAVCC_G11_F12") (pintype "power_in"))
    )
    (net (code "2") (name "FPGA_MGTAVTT") (class "Default")
      (node (ref "C487") (pin "2") (pinfunction "2_2") (pintype "passive"))
      (node (ref "C488") (pin "1") (pinfunction "1_1") (pintype "passive"))
      (node (ref "C489") (pin "1") (pinfunction "1_1") (pintype "passive"))
      (node (ref "C490") (pin "1") (pinfunction "1_1") (pintype "passive"))
      (node (ref "C491") (pin "1") (pinfunction "1_1") (pintype "passive"))
      (node (ref "C492") (pin "1") (pinfunction "1_1") (pintype "passive"))
      (node (ref "C493") (pin "1") (pinfunction "1_1") (pintype "passive"))
      (node (ref "C494") (pin "1") (pinfunction "1_1") (pintype "passive"))
      (node (ref "C495") (pin "1") (pinfunction "1_1") (pintype "passive"))
      (node (ref "C496") (pin "1") (pinfunction "1_1") (pintype "passive"))
      (node (ref "C497") (pin "1") (pinfunction "1_1") (pintype "passive"))
      (node (ref "C498") (pin "1") (pinfunction "1_1") (pintype "passive"))
      (node (ref "C499") (pin "1") (pinfunction "1_1") (pintype "passive"))
      (node (ref "FR101") (pin "1") (pinfunction "1_1") (pintype "passive"))
      (node (ref "IC39") (pin "AD15") (pinfunction "MGTAVTT_G10_AD15") (pintype "power_in"))
      (node (ref "IC39") (pin "AD7") (pinfunction "MGTAVTT_G10_AD7") (pintype "power_in"))
      (node (ref "IC39") (pin "AE10") (pinfunction "MGTAVTT_G10_AE10") (pintype "power_in"))
      (node (ref "IC39") (pin "AE12") (pinfunction "MGTAVTT_G10_AE12") (pintype "power_in"))
      (node (ref "IC39") (pin "AE14") (pinfunction "MGTAVTT_G10_AE14") (pintype "power_in"))
      (node (ref "IC39") (pin "AE8") (pinfunction "MGTAVTT_G10_AE8") (pintype "power_in"))
      (node (ref "IC39") (pin "B10") (pinfunction "MGTAVTT_G11_B10") (pintype "power_in"))
      (node (ref "IC39") (pin "B12") (pinfunction "MGTAVTT_G11_B12") (pintype "power_in"))
      (node (ref "IC39") (pin "B14") (pinfunction "MGTAVTT_G11_B14") (pintype "power_in"))
      (node (ref "IC39") (pin "B8") (pinfunction "MGTAVTT_G11_B8") (pintype "power_in"))
      (node (ref "IC39") (pin "C15") (pinfunction "MGTAVTT_G11_C15") (pintype "power_in"))
      (node (ref "IC39") (pin "C7") (pinfunction "MGTAVTT_G11_C7") (pintype "power_in"))
    )
    (net (code "3") (name "FPGA_VBATT") (class "Default")
      (node (ref "IC39") (pin "G14") (pinfunction "VCCBATT_0_G14") (pintype "power_in"))
      (node (ref "R198") (pin "2") (pinfunction "2_2") (pintype "passive"))
      (node (ref "R199") (pin "2") (pinfunction "2_2") (pintype "passive"))
    )
    (net (code "4") (name "GND") (class "Default")
      (node (ref "BATTH1") (pin "2") (pinfunction "-_2") (pintype "passive"))
      (node (ref "C377") (pin "1") (pinfunction "1_1") (pintype "passive"))
      (node (ref "C378") (pin "1") (pinfunction "1_1") (pintype "passive"))
      (node (ref "C379") (pin "2") (pinfunction "2_2") (pintype "passive"))
      (node (ref "C380") (pin "2") (pinfunction "2_2") (pintype "passive"))
      (node (ref "C381") (pin "1") (pinfunction "1_1") (pintype "passive"))
      (node (ref "C382") (pin "1") (pinfunction "1_1") (pintype "passive"))
      (node (ref "C383") (pin "2") (pinfunction "2_2") (pintype "passive"))
      (node (ref "C384") (pin "2") (pinfunction "2_2") (pintype "passive"))
      (node (ref "C385") (pin "2") (pinfunction "2_2") (pintype "passive"))
      (node (ref "C386") (pin "2") (pinfunction "2_2") (pintype "passive"))
      (node (ref "C387") (pin "2") (pinfunction "2_2") (pintype "passive"))
      (node (ref "C388") (pin "2") (pinfunction "2_2") (pintype "passive"))
      (node (ref "C389") (pin "1") (pinfunction "1_1") (pintype "passive"))
      (node (ref "C390") (pin "1") (pinfunction "1_1") (pintype "passive"))
      (node (ref "C391") (pin "2") (pinfunction "2_2") (pintype "passive"))
      (node (ref "C392") (pin "2") (pinfunction "2_2") (pintype "passive"))
      (node (ref "C393") (pin "2") (pinfunction "2_2") (pintype "passive"))
      (node (ref "C394") (pin "2") (pinfunction "2_2") (pintype "passive"))
      (node (ref "C395") (pin "2") (pinfunction "2_2") (pintype "passive"))
      (node (ref "C396") (pin "2") (pinfunction "2_2") (pintype "passive"))
      (node (ref "C397") (pin "1") (pinfunction "1_1") (pintype "passive"))
      (node (ref "C398") (pin "1") (pinfunction "1_1") (pintype "passive"))
      (node (ref "C399") (pin "2") (pinfunction "2_2") (pintype "passive"))
      (node (ref "C400") (pin "2") (pinfunction "2_2") (pintype "passive"))
      (node (ref "C401") (pin "2") (pinfunction "2_2") (pintype "passive"))
      (node (ref "C402") (pin "2") (pinfunction "2_2") (pintype "passive"))
      (node (ref "C403") (pin "2") (pinfunction "2_2") (pintype "passive"))
      (node (ref "C404") (pin "2") (pinfunction "2_2") (pintype "passive"))
      (node (ref "C405") (pin "1") (pinfunction "1_1") (pintype "passive"))
      (node (ref "C406") (pin "1") (pinfunction "1_1") (pintype "passive"))
      (node (ref "C407") (pin "2") (pinfunction "2_2") (pintype "passive"))
      (node (ref "C408") (pin "2") (pinfunction "2_2") (pintype "passive"))
      (node (ref "C409") (pin "2") (pinfunction "2_2") (pintype "passive"))
      (node (ref "C410") (pin "2") (pinfunction "2_2") (pintype "passive"))
      (node (ref "C411") (pin "2") (pinfunction "2_2") (pintype "passive"))
      (node (ref "C412") (pin "2") (pinfunction "2_2") (pintype "passive"))
      (node (ref "C413") (pin "1") (pinfunction "1_1") (pintype "passive"))
      (node (ref "C414") (pin "1") (pinfunction "1_1") (pintype "passive"))
      (node (ref "C415") (pin "2") (pinfunction "2_2") (pintype "passive"))
      (node (ref "C416") (pin "2") (pinfunction "2_2") (pintype "passive"))
      (node (ref "C417") (pin "2") (pinfunction "2_2") (pintype "passive"))
      (node (ref "C418") (pin "2") (pinfunction "2_2") (pintype "passive"))
      (node (ref "C419") (pin "2") (pinfunction "2_2") (pintype "passive"))
      (node (ref "C420") (pin "2") (pinfunction "2_2") (pintype "passive"))
      (node (ref "C421") (pin "1") (pinfunction "1_1") (pintype "passive"))
      (node (ref "C422") (pin "1") (pinfunction "1_1") (pintype "passive"))
      (node (ref "C423") (pin "2") (pinfunction "2_2") (pintype "passive"))
      (node (ref "C424") (pin "2") (pinfunction "2_2") (pintype "passive"))
      (node (ref "C425") (pin "2") (pinfunction "2_2") (pintype "passive"))
      (node (ref "C426") (pin "2") (pinfunction "2_2") (pintype "passive"))
      (node (ref "C427") (pin "2") (pinfunction "2_2") (pintype "passive"))
      (node (ref "C428") (pin "2") (pinfunction "2_2") (pintype "passive"))
      (node (ref "C429") (pin "1") (pinfunction "1_1") (pintype "passive"))
      (node (ref "C430") (pin "1") (pinfunction "1_1") (pintype "passive"))
      (node (ref "C431") (pin "2") (pinfunction "2_2") (pintype "passive"))
      (node (ref "C432") (pin "2") (pinfunction "2_2") (pintype "passive"))
      (node (ref "C433") (pin "2") (pinfunction "2_2") (pintype "passive"))
      (node (ref "C434") (pin "2") (pinfunction "2_2") (pintype "passive"))
      (node (ref "C435") (pin "2") (pinfunction "2_2") (pintype "passive"))
      (node (ref "C436") (pin "2") (pinfunction "2_2") (pintype "passive"))
      (node (ref "C437") (pin "1") (pinfunction "1_1") (pintype "passive"))
      (node (ref "C438") (pin "1") (pinfunction "1_1") (pintype "passive"))
      (node (ref "C439") (pin "2") (pinfunction "2_2") (pintype "passive"))
      (node (ref "C440") (pin "2") (pinfunction "2_2") (pintype "passive"))
      (node (ref "C441") (pin "2") (pinfunction "2_2") (pintype "passive"))
      (node (ref "C442") (pin "2") (pinfunction "2_2") (pintype "passive"))
      (node (ref "C443") (pin "2") (pinfunction "2_2") (pintype "passive"))
      (node (ref "C444") (pin "2") (pinfunction "2_2") (pintype "passive"))
      (node (ref "C445") (pin "1") (pinfunction "1_1") (pintype "passive"))
      (node (ref "C446") (pin "1") (pinfunction "1_1") (pintype "passive"))
      (node (ref "C447") (pin "1") (pinfunction "1_1") (pintype "passive"))
      (node (ref "C448") (pin "1") (pinfunction "1_1") (pintype "passive"))
      (node (ref "C449") (pin "2") (pinfunction "2_2") (pintype "passive"))
      (node (ref "C450") (pin "2") (pinfunction "2_2") (pintype "passive"))
      (node (ref "C451") (pin "2") (pinfunction "2_2") (pintype "passive"))
      (node (ref "C452") (pin "2") (pinfunction "2_2") (pintype "passive"))
      (node (ref "C453") (pin "2") (pinfunction "2_2") (pintype "passive"))
      (node (ref "C454") (pin "2") (pinfunction "2_2") (pintype "passive"))
      (node (ref "C455") (pin "2") (pinfunction "2_2") (pintype "passive"))
      (node (ref "C456") (pin "2") (pinfunction "2_2") (pintype "passive"))
      (node (ref "C457") (pin "2") (pinfunction "2_2") (pintype "passive"))
      (node (ref "C458") (pin "2") (pinfunction "2_2") (pintype "passive"))
      (node (ref "C459") (pin "2") (pinfunction "2_2") (pintype "passive"))
      (node (ref "C460") (pin "2") (pinfunction "2_2") (pintype "passive"))
      (node (ref "C461") (pin "2") (pinfunction "2_2") (pintype "passive"))
      (node (ref "C462") (pin "1") (pinfunction "1_1") (pintype "passive"))
      (node (ref "C463") (pin "1") (pinfunction "1_1") (pintype "passive"))
      (node (ref "C464") (pin "2") (pinfunction "2_2") (pintype "passive"))
      (node (ref "C465") (pin "2") (pinfunction "2_2") (pintype "passive"))
      (node (ref "C466") (pin "2") (pinfunction "2_2") (pintype "passive"))
      (node (ref "C467") (pin "2") (pinfunction "2_2") (pintype "passive"))
      (node (ref "C468") (pin "2") (pinfunction "2_2") (pintype "passive"))
      (node (ref "C469") (pin "1") (pinfunction "1_1") (pintype "passive"))
      (node (ref "C470") (pin "1") (pinfunction "1_1") (pintype "passive"))
      (node (ref "C471") (pin "1") (pinfunction "1_1") (pintype "passive"))
      (node (ref "C472") (pin "2") (pinfunction "2_2") (pintype "passive"))
      (node (ref "C473") (pin "2") (pinfunction "2_2") (pintype "passive"))
      (node (ref "C474") (pin "2") (pinfunction "2_2") (pintype "passive"))
      (node (ref "C475") (pin "2") (pinfunction "2_2") (pintype "passive"))
      (node (ref "C476") (pin "1") (pinfunction "1_1") (pintype "passive"))
      (node (ref "C477") (pin "2") (pinfunction "2_2") (pintype "passive"))
      (node (ref "C478") (pin "2") (pinfunction "2_2") (pintype "passive"))
      (node (ref "C479") (pin "2") (pinfunction "2_2") (pintype "passive"))
      (node (ref "C480") (pin "2") (pinfunction "2_2") (pintype "passive"))
      (node (ref "C481") (pin "2") (pinfunction "2_2") (pintype "passive"))
      (node (ref "C482") (pin "2") (pinfunction "2_2") (pintype "passive"))
      (node (ref "C483") (pin "2") (pinfunction "2_2") (pintype "passive"))
      (node (ref "C484") (pin "2") (pinfunction "2_2") (pintype "passive"))
      (node (ref "C485") (pin "2") (pinfunction "2_2") (pintype "passive"))
      (node (ref "C486") (pin "2") (pinfunction "2_2") (pintype "passive"))
      (node (ref "C487") (pin "1") (pinfunction "1_1") (pintype "passive"))
      (node (ref "C488") (pin "2") (pinfunction "2_2") (pintype "passive"))
      (node (ref "C489") (pin "2") (pinfunction "2_2") (pintype "passive"))
      (node (ref "C490") (pin "2") (pinfunction "2_2") (pintype "passive"))
      (node (ref "C491") (pin "2") (pinfunction "2_2") (pintype "passive"))
      (node (ref "C492") (pin "2") (pinfunction "2_2") (pintype "passive"))
      (node (ref "C493") (pin "2") (pinfunction "2_2") (pintype "passive"))
      (node (ref "C494") (pin "2") (pinfunction "2_2") (pintype "passive"))
      (node (ref "C495") (pin "2") (pinfunction "2_2") (pintype "passive"))
      (node (ref "C496") (pin "2") (pinfunction "2_2") (pintype "passive"))
      (node (ref "C497") (pin "2") (pinfunction "2_2") (pintype "passive"))
      (node (ref "C498") (pin "2") (pinfunction "2_2") (pintype "passive"))
      (node (ref "C499") (pin "2") (pinfunction "2_2") (pintype "passive"))
      (node (ref "FR103") (pin "1") (pinfunction "1_1") (pintype "passive"))
      (node (ref "IC39") (pin "A10") (pinfunction "GND_A10") (pintype "power_in"))
      (node (ref "IC39") (pin "A12") (pinfunction "GND_A12") (pintype "power_in"))
      (node (ref "IC39") (pin "A14") (pinfunction "GND_A14") (pintype "power_in"))
      (node (ref "IC39") (pin "A16") (pinfunction "GND_A16") (pintype "power_in"))
      (node (ref "IC39") (pin "A26") (pinfunction "GND_A26") (pintype "power_in"))
      (node (ref "IC39") (pin "A6") (pinfunction "GND_A6") (pintype "power_in"))
      (node (ref "IC39") (pin "A8") (pinfunction "GND_A8") (pintype "power_in"))
      (node (ref "IC39") (pin "AA14") (pinfunction "GND_AA14") (pintype "power_in"))
      (node (ref "IC39") (pin "AA16") (pinfunction "GND_AA16") (pintype "power_in"))
      (node (ref "IC39") (pin "AA26") (pinfunction "GND_AA26") (pintype "power_in"))
      (node (ref "IC39") (pin "AA6") (pinfunction "GND_AA6") (pintype "power_in"))
      (node (ref "IC39") (pin "AA9") (pinfunction "GND_AA9") (pintype "power_in"))
      (node (ref "IC39") (pin "AB10") (pinfunction "GND_AB10") (pintype "power_in"))
      (node (ref "IC39") (pin "AB12") (pinfunction "GND_AB12") (pintype "power_in"))
      (node (ref "IC39") (pin "AB14") (pinfunction "GND_AB14") (pintype "power_in"))
      (node (ref "IC39") (pin "AB23") (pinfunction "GND_AB23") (pintype "power_in"))
      (node (ref "IC39") (pin "AB3") (pinfunction "GND_AB3") (pintype "power_in"))
      (node (ref "IC39") (pin "AB8") (pinfunction "GND_AB8") (pintype "power_in"))
      (node (ref "IC39") (pin "AB9") (pinfunction "GND_AB9") (pintype "power_in"))
      (node (ref "IC39") (pin "AC15") (pinfunction "GND_AC15") (pintype "power_in"))
      (node (ref "IC39") (pin "AC20") (pinfunction "GND_AC20") (pintype "power_in"))
      (node (ref "IC39") (pin "AC7") (pinfunction "GND_AC7") (pintype "power_in"))
      (node (ref "IC39") (pin "AD11") (pinfunction "GND_AD11") (pintype "power_in"))
      (node (ref "IC39") (pin "AD13") (pinfunction "GND_AD13") (pintype "power_in"))
      (node (ref "IC39") (pin "AD16") (pinfunction "GND_AD16") (pintype "power_in"))
      (node (ref "IC39") (pin "AD6") (pinfunction "GND_AD6") (pintype "power_in"))
      (node (ref "IC39") (pin "AD9") (pinfunction "GND_AD9") (pintype "power_in"))
      (node (ref "IC39") (pin "AE15") (pinfunction "GND_AE15") (pintype "power_in"))
      (node (ref "IC39") (pin "AE24") (pinfunction "GND_AE24") (pintype "power_in"))
      (node (ref "IC39") (pin "AE4") (pinfunction "GND_AE4") (pintype "power_in"))
      (node (ref "IC39") (pin "AE6") (pinfunction "GND_AE6") (pintype "power_in"))
      (node (ref "IC39") (pin "AF1") (pinfunction "GND_AF1") (pintype "power_in"))
      (node (ref "IC39") (pin "AF10") (pinfunction "GND_AF10") (pintype "power_in"))
      (node (ref "IC39") (pin "AF12") (pinfunction "GND_AF12") (pintype "power_in"))
      (node (ref "IC39") (pin "AF14") (pinfunction "GND_AF14") (pintype "power_in"))
      (node (ref "IC39") (pin "AF16") (pinfunction "GND_AF16") (pintype "power_in"))
      (node (ref "IC39") (pin "AF21") (pinfunction "GND_AF21") (pintype "power_in"))
      (node (ref "IC39") (pin "AF6") (pinfunction "GND_AF6") (pintype "power_in"))
      (node (ref "IC39") (pin "AF8") (pinfunction "GND_AF8") (pintype "power_in"))
      (node (ref "IC39") (pin "B15") (pinfunction "GND_B15") (pintype "power_in"))
      (node (ref "IC39") (pin "B16") (pinfunction "GND_B16") (pintype "power_in"))
      (node (ref "IC39") (pin "B23") (pinfunction "GND_B23") (pintype "power_in"))
      (node (ref "IC39") (pin "B3") (pinfunction "GND_B3") (pintype "power_in"))
      (node (ref "IC39") (pin "B6") (pinfunction "GND_B6") (pintype "power_in"))
      (node (ref "IC39") (pin "C11") (pinfunction "GND_C11") (pintype "power_in"))
      (node (ref "IC39") (pin "C13") (pinfunction "GND_C13") (pintype "power_in"))
      (node (ref "IC39") (pin "C16") (pinfunction "GND_C16") (pintype "power_in"))
      (node (ref "IC39") (pin "C20") (pinfunction "GND_C20") (pintype "power_in"))
      (node (ref "IC39") (pin "C6") (pinfunction "GND_C6") (pintype "power_in"))
      (node (ref "IC39") (pin "C9") (pinfunction "GND_C9") (pintype "power_in"))
      (node (ref "IC39") (pin "D15") (pinfunction "GND_D15") (pintype "power_in"))
      (node (ref "IC39") (pin "D17") (pinfunction "GND_D17") (pintype "power_in"))
      (node (ref "IC39") (pin "D7") (pinfunction "GND_D7") (pintype "power_in"))
      (node (ref "IC39") (pin "E10") (pinfunction "GND_E10") (pintype "power_in"))
      (node (ref "IC39") (pin "E12") (pinfunction "GND_E12") (pintype "power_in"))
      (node (ref "IC39") (pin "E14") (pinfunction "GND_E14") (pintype "power_in"))
      (node (ref "IC39") (pin "E15") (pinfunction "GND_E15") (pintype "power_in"))
      (node (ref "IC39") (pin "E24") (pinfunction "GND_E24") (pintype "power_in"))
      (node (ref "IC39") (pin "E4") (pinfunction "GND_E4") (pintype "power_in"))
      (node (ref "IC39") (pin "E7") (pinfunction "GND_E7") (pintype "power_in"))
      (node (ref "IC39") (pin "E8") (pinfunction "GND_E8") (pintype "power_in"))
      (node (ref "IC39") (pin "E9") (pinfunction "GND_E9") (pintype "power_in"))
      (node (ref "IC39") (pin "F1") (pinfunction "GND_F1") (pintype "power_in"))
      (node (ref "IC39") (pin "F14") (pinfunction "GND_F14") (pintype "power_in"))
      (node (ref "IC39") (pin "F21") (pinfunction "GND_F21") (pintype "power_in"))
      (node (ref "IC39") (pin "F9") (pinfunction "GND_F9") (pintype "power_in"))
      (node (ref "IC39") (pin "G10") (pinfunction "GND_G10") (pintype "power_in"))
      (node (ref "IC39") (pin "G11") (pinfunction "GND_G11") (pintype "power_in"))
      (node (ref "IC39") (pin "G12") (pinfunction "GND_G12") (pintype "power_in"))
      (node (ref "IC39") (pin "G13") (pinfunction "GND_G13") (pintype "power_in"))
      (node (ref "IC39") (pin "G18") (pinfunction "GND_G18") (pintype "power_in"))
      (node (ref "IC39") (pin "H25") (pinfunction "GND_H25") (pintype "power_in"))
      (node (ref "IC39") (pin "H5") (pinfunction "GND_H5") (pintype "power_in"))
      (node (ref "IC39") (pin "J12") (pinfunction "GND_J12") (pintype "power_in"))
      (node (ref "IC39") (pin "J2") (pinfunction "GND_J2") (pintype "power_in"))
      (node (ref "IC39") (pin "J22") (pinfunction "GND_J22") (pintype "power_in"))
      (node (ref "IC39") (pin "K11") (pinfunction "GND_K11") (pintype "power_in"))
      (node (ref "IC39") (pin "K13") (pinfunction "GND_K13") (pintype "power_in"))
      (node (ref "IC39") (pin "K19") (pinfunction "GND_K19") (pintype "power_in"))
      (node (ref "IC39") (pin "K9") (pinfunction "GND_K9") (pintype "power_in"))
      (node (ref "IC39") (pin "L10") (pinfunction "GND_L10") (pintype "power_in"))
      (node (ref "IC39") (pin "L12") (pinfunction "GND_L12") (pintype "power_in"))
      (node (ref "IC39") (pin "L16") (pinfunction "GND_L16") (pintype "power_in"))
      (node (ref "IC39") (pin "L26") (pinfunction "GND_L26") (pintype "power_in"))
      (node (ref "IC39") (pin "L6") (pinfunction "GND_L6") (pintype "power_in"))
      (node (ref "IC39") (pin "M13") (pinfunction "GND_M13") (pintype "power_in"))
      (node (ref "IC39") (pin "M23") (pinfunction "GND_M23") (pintype "power_in"))
      (node (ref "IC39") (pin "M3") (pinfunction "GND_M3") (pintype "power_in"))
      (node (ref "IC39") (pin "M9") (pinfunction "GND_M9") (pintype "power_in"))
      (node (ref "IC39") (pin "N10") (pinfunction "GND_N10") (pintype "power_in"))
      (node (ref "IC39") (pin "N20") (pinfunction "GND_N20") (pintype "power_in"))
      (node (ref "IC39") (pin "P13") (pinfunction "GND_P13") (pintype "power_in"))
      (node (ref "IC39") (pin "P17") (pinfunction "GND_P17") (pintype "power_in"))
      (node (ref "IC39") (pin "P7") (pinfunction "GND_P7") (pintype "power_in"))
      (node (ref "IC39") (pin "P9") (pinfunction "GND_P9") (pintype "power_in"))
      (node (ref "IC39") (pin "R10") (pinfunction "GND_R10") (pintype "power_in"))
      (node (ref "IC39") (pin "R24") (pinfunction "GND_R24") (pintype "power_in"))
      (node (ref "IC39") (pin "R4") (pinfunction "GND_R4") (pintype "power_in"))
      (node (ref "IC39") (pin "T1") (pinfunction "GND_T1") (pintype "power_in"))
      (node (ref "IC39") (pin "T11") (pinfunction "GND_T11") (pintype "power_in"))
      (node (ref "IC39") (pin "T13") (pinfunction "GND_T13") (pintype "power_in"))
      (node (ref "IC39") (pin "T21") (pinfunction "GND_T21") (pintype "power_in"))
      (node (ref "IC39") (pin "T9") (pinfunction "GND_T9") (pintype "power_in"))
      (node (ref "IC39") (pin "U10") (pinfunction "GND_U10") (pintype "power_in"))
      (node (ref "IC39") (pin "U12") (pinfunction "GND_U12") (pintype "power_in"))
      (node (ref "IC39") (pin "U18") (pinfunction "GND_U18") (pintype "power_in"))
      (node (ref "IC39") (pin "U8") (pinfunction "GND_U8") (pintype "power_in"))
      (node (ref "IC39") (pin "V13") (pinfunction "GND_V13") (pintype "power_in"))
      (node (ref "IC39") (pin "V15") (pinfunction "GND_V15") (pintype "power_in"))
      (node (ref "IC39") (pin "V25") (pinfunction "GND_V25") (pintype "power_in"))
      (node (ref "IC39") (pin "V5") (pinfunction "GND_V5") (pintype "power_in"))
      (node (ref "IC39") (pin "W12") (pinfunction "GND_W12") (pintype "power_in"))
      (node (ref "IC39") (pin "W2") (pinfunction "GND_W2") (pintype "power_in"))
      (node (ref "IC39") (pin "W22") (pinfunction "GND_W22") (pintype "power_in"))
      (node (ref "IC39") (pin "Y10") (pinfunction "GND_Y10") (pintype "power_in"))
      (node (ref "IC39") (pin "Y11") (pinfunction "GND_Y11") (pintype "power_in"))
      (node (ref "IC39") (pin "Y12") (pinfunction "GND_Y12") (pintype "power_in"))
      (node (ref "IC39") (pin "Y13") (pinfunction "GND_Y13") (pintype "power_in"))
      (node (ref "IC39") (pin "Y19") (pinfunction "GND_Y19") (pintype "power_in"))
    )
    (net (code "5") (name "GND_ADC") (class "Default")
      (node (ref "C500") (pin "1") (pinfunction "1_1") (pintype "passive"))
      (node (ref "C501") (pin "2") (pinfunction "2_2") (pintype "passive"))
      (node (ref "FR103") (pin "2") (pinfunction "2_2") (pintype "passive"))
      (node (ref "IC39") (pin "M11") (pinfunction "GNDADC_0_M11") (pintype "power_in"))
    )
    (net (code "6") (name "Net-(BATTH1-+)") (class "Default")
      (node (ref "BATTH1") (pin "1") (pinfunction "+_1") (pintype "passive"))
      (node (ref "R199") (pin "1") (pinfunction "1_1") (pintype "passive"))
    )
    (net (code "7") (name "VCC1P0") (class "Default")
      (node (ref "C469") (pin "2") (pinfunction "2_2") (pintype "passive"))
      (node (ref "C470") (pin "2") (pinfunction "2_2") (pintype "passive"))
      (node (ref "C471") (pin "2") (pinfunction "2_2") (pintype "passive"))
      (node (ref "C472") (pin "1") (pinfunction "1_1") (pintype "passive"))
      (node (ref "C473") (pin "1") (pinfunction "1_1") (pintype "passive"))
      (node (ref "C474") (pin "1") (pinfunction "1_1") (pintype "passive"))
      (node (ref "C475") (pin "1") (pinfunction "1_1") (pintype "passive"))
      (node (ref "FR100") (pin "2") (pinfunction "2_2") (pintype "passive"))
      (node (ref "IC39") (pin "N13") (pinfunction "VCCBRAM_N13") (pintype "power_in"))
      (node (ref "IC39") (pin "R13") (pinfunction "VCCBRAM_R13") (pintype "power_in"))
      (node (ref "IC39") (pin "U13") (pinfunction "VCCBRAM_U13") (pintype "power_in"))
      (node (ref "IC39") (pin "W13") (pinfunction "VCCBRAM_W13") (pintype "power_in"))
    )
    (net (code "8") (name "VCC1P0_INT") (class "Default")
      (node (ref "C445") (pin "2") (pinfunction "2_2") (pintype "passive"))
      (node (ref "C446") (pin "2") (pinfunction "2_2") (pintype "passive"))
      (node (ref "C447") (pin "2") (pinfunction "2_2") (pintype "passive"))
      (node (ref "C448") (pin "2") (pinfunction "2_2") (pintype "passive"))
      (node (ref "C449") (pin "1") (pinfunction "1_1") (pintype "passive"))
      (node (ref "C450") (pin "1") (pinfunction "1_1") (pintype "passive"))
      (node (ref "C451") (pin "1") (pinfunction "1_1") (pintype "passive"))
      (node (ref "C452") (pin "1") (pinfunction "1_1") (pintype "passive"))
      (node (ref "C453") (pin "1") (pinfunction "1_1") (pintype "passive"))
      (node (ref "C454") (pin "1") (pinfunction "1_1") (pintype "passive"))
      (node (ref "C455") (pin "1") (pinfunction "1_1") (pintype "passive"))
      (node (ref "C456") (pin "1") (pinfunction "1_1") (pintype "passive"))
      (node (ref "C457") (pin "1") (pinfunction "1_1") (pintype "passive"))
      (node (ref "C458") (pin "1") (pinfunction "1_1") (pintype "passive"))
      (node (ref "C459") (pin "1") (pinfunction "1_1") (pintype "passive"))
      (node (ref "C460") (pin "1") (pinfunction "1_1") (pintype "passive"))
      (node (ref "C461") (pin "1") (pinfunction "1_1") (pintype "passive"))
      (node (ref "IC39") (pin "J11") (pinfunction "VCCINT_J11") (pintype "power_in"))
      (node (ref "IC39") (pin "J13") (pinfunction "VCCINT_J13") (pintype "power_in"))
      (node (ref "IC39") (pin "K10") (pinfunction "VCCINT_K10") (pintype "power_in"))
      (node (ref "IC39") (pin "K12") (pinfunction "VCCINT_K12") (pintype "power_in"))
      (node (ref "IC39") (pin "L11") (pinfunction "VCCINT_L11") (pintype "power_in"))
      (node (ref "IC39") (pin "L13") (pinfunction "VCCINT_L13") (pintype "power_in"))
      (node (ref "IC39") (pin "M10") (pinfunction "VCCINT_M10") (pintype "power_in"))
      (node (ref "IC39") (pin "P10") (pinfunction "VCCINT_P10") (pintype "power_in"))
      (node (ref "IC39") (pin "T10") (pinfunction "VCCINT_T10") (pintype "power_in"))
      (node (ref "IC39") (pin "T12") (pinfunction "VCCINT_T12") (pintype "power_in"))
      (node (ref "IC39") (pin "U11") (pinfunction "VCCINT_U11") (pintype "power_in"))
      (node (ref "IC39") (pin "V10") (pinfunction "VCCINT_V10") (pintype "power_in"))
      (node (ref "IC39") (pin "V12") (pinfunction "VCCINT_V12") (pintype "power_in"))
    )
    (net (code "9") (name "VCC1P2") (class "Default")
      (node (ref "FR101") (pin "2") (pinfunction "2_2") (pintype "passive"))
    )
    (net (code "10") (name "VCC1P8") (class "Default")
      (node (ref "C462") (pin "2") (pinfunction "2_2") (pintype "passive"))
      (node (ref "C463") (pin "2") (pinfunction "2_2") (pintype "passive"))
      (node (ref "C464") (pin "1") (pinfunction "1_1") (pintype "passive"))
      (node (ref "C465") (pin "1") (pinfunction "1_1") (pintype "passive"))
      (node (ref "C466") (pin "1") (pinfunction "1_1") (pintype "passive"))
      (node (ref "C467") (pin "1") (pinfunction "1_1") (pintype "passive"))
      (node (ref "C468") (pin "1") (pinfunction "1_1") (pintype "passive"))
      (node (ref "FR102") (pin "1") (pinfunction "1_1") (pintype "passive"))
      (node (ref "IC39") (pin "J9") (pinfunction "VCCAUX_J9") (pintype "power_in"))
      (node (ref "IC39") (pin "L9") (pinfunction "VCCAUX_L9") (pintype "power_in"))
      (node (ref "IC39") (pin "N9") (pinfunction "VCCAUX_N9") (pintype "power_in"))
      (node (ref "IC39") (pin "R9") (pinfunction "VCCAUX_R9") (pintype "power_in"))
      (node (ref "IC39") (pin "U9") (pinfunction "VCCAUX_U9") (pintype "power_in"))
      (node (ref "R198") (pin "1") (pinfunction "1_1") (pintype "passive"))
    )
    (net (code "11") (name "VCC1P8_FADC") (class "Default")
      (node (ref "C500") (pin "2") (pinfunction "2_2") (pintype "passive"))
      (node (ref "C501") (pin "1") (pinfunction "1_1") (pintype "passive"))
      (node (ref "FR102") (pin "2") (pinfunction "2_2") (pintype "passive"))
      (node (ref "IC39") (pin "M12") (pinfunction "VCCADC_0_M12") (pintype "power_in"))
    )
    (net (code "12") (name "VCC2P5") (class "Default")
      (node (ref "C381") (pin "2") (pinfunction "2_2") (pintype "passive"))
      (node (ref "C382") (pin "2") (pinfunction "2_2") (pintype "passive"))
      (node (ref "C383") (pin "1") (pinfunction "1_1") (pintype "passive"))
      (node (ref "C384") (pin "1") (pinfunction "1_1") (pintype "passive"))
      (node (ref "C385") (pin "1") (pinfunction "1_1") (pintype "passive"))
      (node (ref "C386") (pin "1") (pinfunction "1_1") (pintype "passive"))
      (node (ref "C387") (pin "1") (pinfunction "1_1") (pintype "passive"))
      (node (ref "C388") (pin "1") (pinfunction "1_1") (pintype "passive"))
      (node (ref "C389") (pin "2") (pinfunction "2_2") (pintype "passive"))
      (node (ref "C390") (pin "2") (pinfunction "2_2") (pintype "passive"))
      (node (ref "C391") (pin "1") (pinfunction "1_1") (pintype "passive"))
      (node (ref "C392") (pin "1") (pinfunction "1_1") (pintype "passive"))
      (node (ref "C393") (pin "1") (pinfunction "1_1") (pintype "passive"))
      (node (ref "C394") (pin "1") (pinfunction "1_1") (pintype "passive"))
      (node (ref "C395") (pin "1") (pinfunction "1_1") (pintype "passive"))
      (node (ref "C396") (pin "1") (pinfunction "1_1") (pintype "passive"))
      (node (ref "C405") (pin "2") (pinfunction "2_2") (pintype "passive"))
      (node (ref "C406") (pin "2") (pinfunction "2_2") (pintype "passive"))
      (node (ref "C407") (pin "1") (pinfunction "1_1") (pintype "passive"))
      (node (ref "C408") (pin "1") (pinfunction "1_1") (pintype "passive"))
      (node (ref "C409") (pin "1") (pinfunction "1_1") (pintype "passive"))
      (node (ref "C410") (pin "1") (pinfunction "1_1") (pintype "passive"))
      (node (ref "C411") (pin "1") (pinfunction "1_1") (pintype "passive"))
      (node (ref "C412") (pin "1") (pinfunction "1_1") (pintype "passive"))
      (node (ref "C421") (pin "2") (pinfunction "2_2") (pintype "passive"))
      (node (ref "C422") (pin "2") (pinfunction "2_2") (pintype "passive"))
      (node (ref "C423") (pin "1") (pinfunction "1_1") (pintype "passive"))
      (node (ref "C424") (pin "1") (pinfunction "1_1") (pintype "passive"))
      (node (ref "C425") (pin "1") (pinfunction "1_1") (pintype "passive"))
      (node (ref "C426") (pin "1") (pinfunction "1_1") (pintype "passive"))
      (node (ref "C427") (pin "1") (pinfunction "1_1") (pintype "passive"))
      (node (ref "C428") (pin "1") (pinfunction "1_1") (pintype "passive"))
      (node (ref "C429") (pin "2") (pinfunction "2_2") (pintype "passive"))
      (node (ref "C430") (pin "2") (pinfunction "2_2") (pintype "passive"))
      (node (ref "C431") (pin "1") (pinfunction "1_1") (pintype "passive"))
      (node (ref "C432") (pin "1") (pinfunction "1_1") (pintype "passive"))
      (node (ref "C433") (pin "1") (pinfunction "1_1") (pintype "passive"))
      (node (ref "C434") (pin "1") (pinfunction "1_1") (pintype "passive"))
      (node (ref "C435") (pin "1") (pinfunction "1_1") (pintype "passive"))
      (node (ref "C436") (pin "1") (pinfunction "1_1") (pintype "passive"))
      (node (ref "C437") (pin "2") (pinfunction "2_2") (pintype "passive"))
      (node (ref "C438") (pin "2") (pinfunction "2_2") (pintype "passive"))
      (node (ref "C439") (pin "1") (pinfunction "1_1") (pintype "passive"))
      (node (ref "C440") (pin "1") (pinfunction "1_1") (pintype "passive"))
      (node (ref "C441") (pin "1") (pinfunction "1_1") (pintype "passive"))
      (node (ref "C442") (pin "1") (pinfunction "1_1") (pintype "passive"))
      (node (ref "C443") (pin "1") (pinfunction "1_1") (pintype "passive"))
      (node (ref "C444") (pin "1") (pinfunction "1_1") (pintype "passive"))
      (node (ref "IC39") (pin "A1") (pinfunction "VCCO_35_A1") (pintype "power_in"))
      (node (ref "IC39") (pin "A21") (pinfunction "VCCO_16_A21") (pintype "power_in"))
      (node (ref "IC39") (pin "AA21") (pinfunction "VCCO_12_AA21") (pintype "power_in"))
      (node (ref "IC39") (pin "AB18") (pinfunction "VCCO_12_AB18") (pintype "power_in"))
      (node (ref "IC39") (pin "AC25") (pinfunction "VCCO_13_AC25") (pintype "power_in"))
      (node (ref "IC39") (pin "AD22") (pinfunction "VCCO_12_AD22") (pintype "power_in"))
      (node (ref "IC39") (pin "AE19") (pinfunction "VCCO_12_AE19") (pintype "power_in"))
      (node (ref "IC39") (pin "AF26") (pinfunction "VCCO_12_AF26") (pintype "power_in"))
      (node (ref "IC39") (pin "B18") (pinfunction "VCCO_16_B18") (pintype "power_in"))
      (node (ref "IC39") (pin "C25") (pinfunction "VCCO_16_C25") (pintype "power_in"))
      (node (ref "IC39") (pin "C5") (pinfunction "VCCO_35_C5") (pintype "power_in"))
      (node (ref "IC39") (pin "D2") (pinfunction "VCCO_35_D2") (pintype "power_in"))
      (node (ref "IC39") (pin "D22") (pinfunction "VCCO_16_D22") (pintype "power_in"))
      (node (ref "IC39") (pin "E19") (pinfunction "VCCO_16_E19") (pintype "power_in"))
      (node (ref "IC39") (pin "F16") (pinfunction "VCCO_16_F16") (pintype "power_in"))
      (node (ref "IC39") (pin "F26") (pinfunction "VCCO_15_F26") (pintype "power_in"))
      (node (ref "IC39") (pin "F6") (pinfunction "VCCO_35_F6") (pintype "power_in"))
      (node (ref "IC39") (pin "G23") (pinfunction "VCCO_15_G23") (pintype "power_in"))
      (node (ref "IC39") (pin "G3") (pinfunction "VCCO_35_G3") (pintype "power_in"))
      (node (ref "IC39") (pin "H20") (pinfunction "VCCO_15_H20") (pintype "power_in"))
      (node (ref "IC39") (pin "J17") (pinfunction "VCCO_15_J17") (pintype "power_in"))
      (node (ref "IC39") (pin "J7") (pinfunction "VCCO_35_J7") (pintype "power_in"))
      (node (ref "IC39") (pin "K14") (pinfunction "VCCO_15_K14") (pintype "power_in"))
      (node (ref "IC39") (pin "K4") (pinfunction "VCCO_34_K4") (pintype "power_in"))
      (node (ref "IC39") (pin "L1") (pinfunction "VCCO_34_L1") (pintype "power_in"))
      (node (ref "IC39") (pin "M18") (pinfunction "VCCO_15_M18") (pintype "power_in"))
      (node (ref "IC39") (pin "M8") (pinfunction "VCCO_34_M8") (pintype "power_in"))
      (node (ref "IC39") (pin "N5") (pinfunction "VCCO_34_N5") (pintype "power_in"))
      (node (ref "IC39") (pin "P2") (pinfunction "VCCO_34_P2") (pintype "power_in"))
      (node (ref "IC39") (pin "T16") (pinfunction "VCCO_13_T16") (pintype "power_in"))
      (node (ref "IC39") (pin "T26") (pinfunction "VCCO_13_T26") (pintype "power_in"))
      (node (ref "IC39") (pin "T6") (pinfunction "VCCO_34_T6") (pintype "power_in"))
      (node (ref "IC39") (pin "U23") (pinfunction "VCCO_13_U23") (pintype "power_in"))
      (node (ref "IC39") (pin "V20") (pinfunction "VCCO_13_V20") (pintype "power_in"))
      (node (ref "IC39") (pin "W17") (pinfunction "VCCO_12_W17") (pintype "power_in"))
      (node (ref "IC39") (pin "Y24") (pinfunction "VCCO_13_Y24") (pintype "power_in"))
    )
    (net (code "13") (name "VCC3P3") (class "Default")
      (node (ref "C377") (pin "2") (pinfunction "2_2") (pintype "passive"))
      (node (ref "C378") (pin "2") (pinfunction "2_2") (pintype "passive"))
      (node (ref "C379") (pin "1") (pinfunction "1_1") (pintype "passive"))
      (node (ref "C380") (pin "1") (pinfunction "1_1") (pintype "passive"))
      (node (ref "C413") (pin "2") (pinfunction "2_2") (pintype "passive"))
      (node (ref "C414") (pin "2") (pinfunction "2_2") (pintype "passive"))
      (node (ref "C415") (pin "1") (pinfunction "1_1") (pintype "passive"))
      (node (ref "C416") (pin "1") (pinfunction "1_1") (pintype "passive"))
      (node (ref "C417") (pin "1") (pinfunction "1_1") (pintype "passive"))
      (node (ref "C418") (pin "1") (pinfunction "1_1") (pintype "passive"))
      (node (ref "C419") (pin "1") (pinfunction "1_1") (pintype "passive"))
      (node (ref "C420") (pin "1") (pinfunction "1_1") (pintype "passive"))
      (node (ref "IC39") (pin "K24") (pinfunction "VCCO_14_K24") (pintype "power_in"))
      (node (ref "IC39") (pin "L21") (pinfunction "VCCO_14_L21") (pintype "power_in"))
      (node (ref "IC39") (pin "N15") (pinfunction "VCCO_14_N15") (pintype "power_in"))
      (node (ref "IC39") (pin "N25") (pinfunction "VCCO_14_N25") (pintype "power_in"))
      (node (ref "IC39") (pin "P22") (pinfunction "VCCO_14_P22") (pintype "power_in"))
      (node (ref "IC39") (pin "R19") (pinfunction "VCCO_14_R19") (pintype "power_in"))
      (node (ref "IC39") (pin "W11") (pinfunction "VCCO_0_W11") (pintype "power_in"))
      (node (ref "IC39") (pin "Y14") (pinfunction "VCCO_0_Y14") (pintype "power_in"))
    )
    (net (code "14") (name "VDIO_LMS_FPGA") (class "Default")
      (node (ref "C397") (pin "2") (pinfunction "2_2") (pintype "passive"))
      (node (ref "C398") (pin "2") (pinfunction "2_2") (pintype "passive"))
      (node (ref "C399") (pin "1") (pinfunction "1_1") (pintype "passive"))
      (node (ref "C400") (pin "1") (pinfunction "1_1") (pintype "passive"))
      (node (ref "C401") (pin "1") (pinfunction "1_1") (pintype "passive"))
      (node (ref "C402") (pin "1") (pinfunction "1_1") (pintype "passive"))
      (node (ref "C403") (pin "1") (pinfunction "1_1") (pintype "passive"))
      (node (ref "C404") (pin "1") (pinfunction "1_1") (pintype "passive"))
      (node (ref "IC39") (pin "AA1") (pinfunction "VCCO_33_AA1") (pintype "power_in"))
      (node (ref "IC39") (pin "AC5") (pinfunction "VCCO_33_AC5") (pintype "power_in"))
      (node (ref "IC39") (pin "AD2") (pinfunction "VCCO_33_AD2") (pintype "power_in"))
      (node (ref "IC39") (pin "U3") (pinfunction "VCCO_33_U3") (pintype "power_in"))
      (node (ref "IC39") (pin "W7") (pinfunction "VCCO_33_W7") (pintype "power_in"))
      (node (ref "IC39") (pin "Y4") (pinfunction "VCCO_33_Y4") (pintype "power_in"))
    )
    (net (code "15") (name "unconnected-(BATT1-PadNEGATIVE)") (class "Default")
      (node (ref "BATT1") (pin "NEGATIVE") (pintype "passive+no_connect"))
    )
    (net (code "16") (name "unconnected-(BATT1-PadPOSITIVE)") (class "Default")
      (node (ref "BATT1") (pin "POSITIVE") (pintype "passive+no_connect"))
    )
  )
)
